# Pro-Mini-Candy.net
KiCad netlist of a schematic drawn in EAGLE
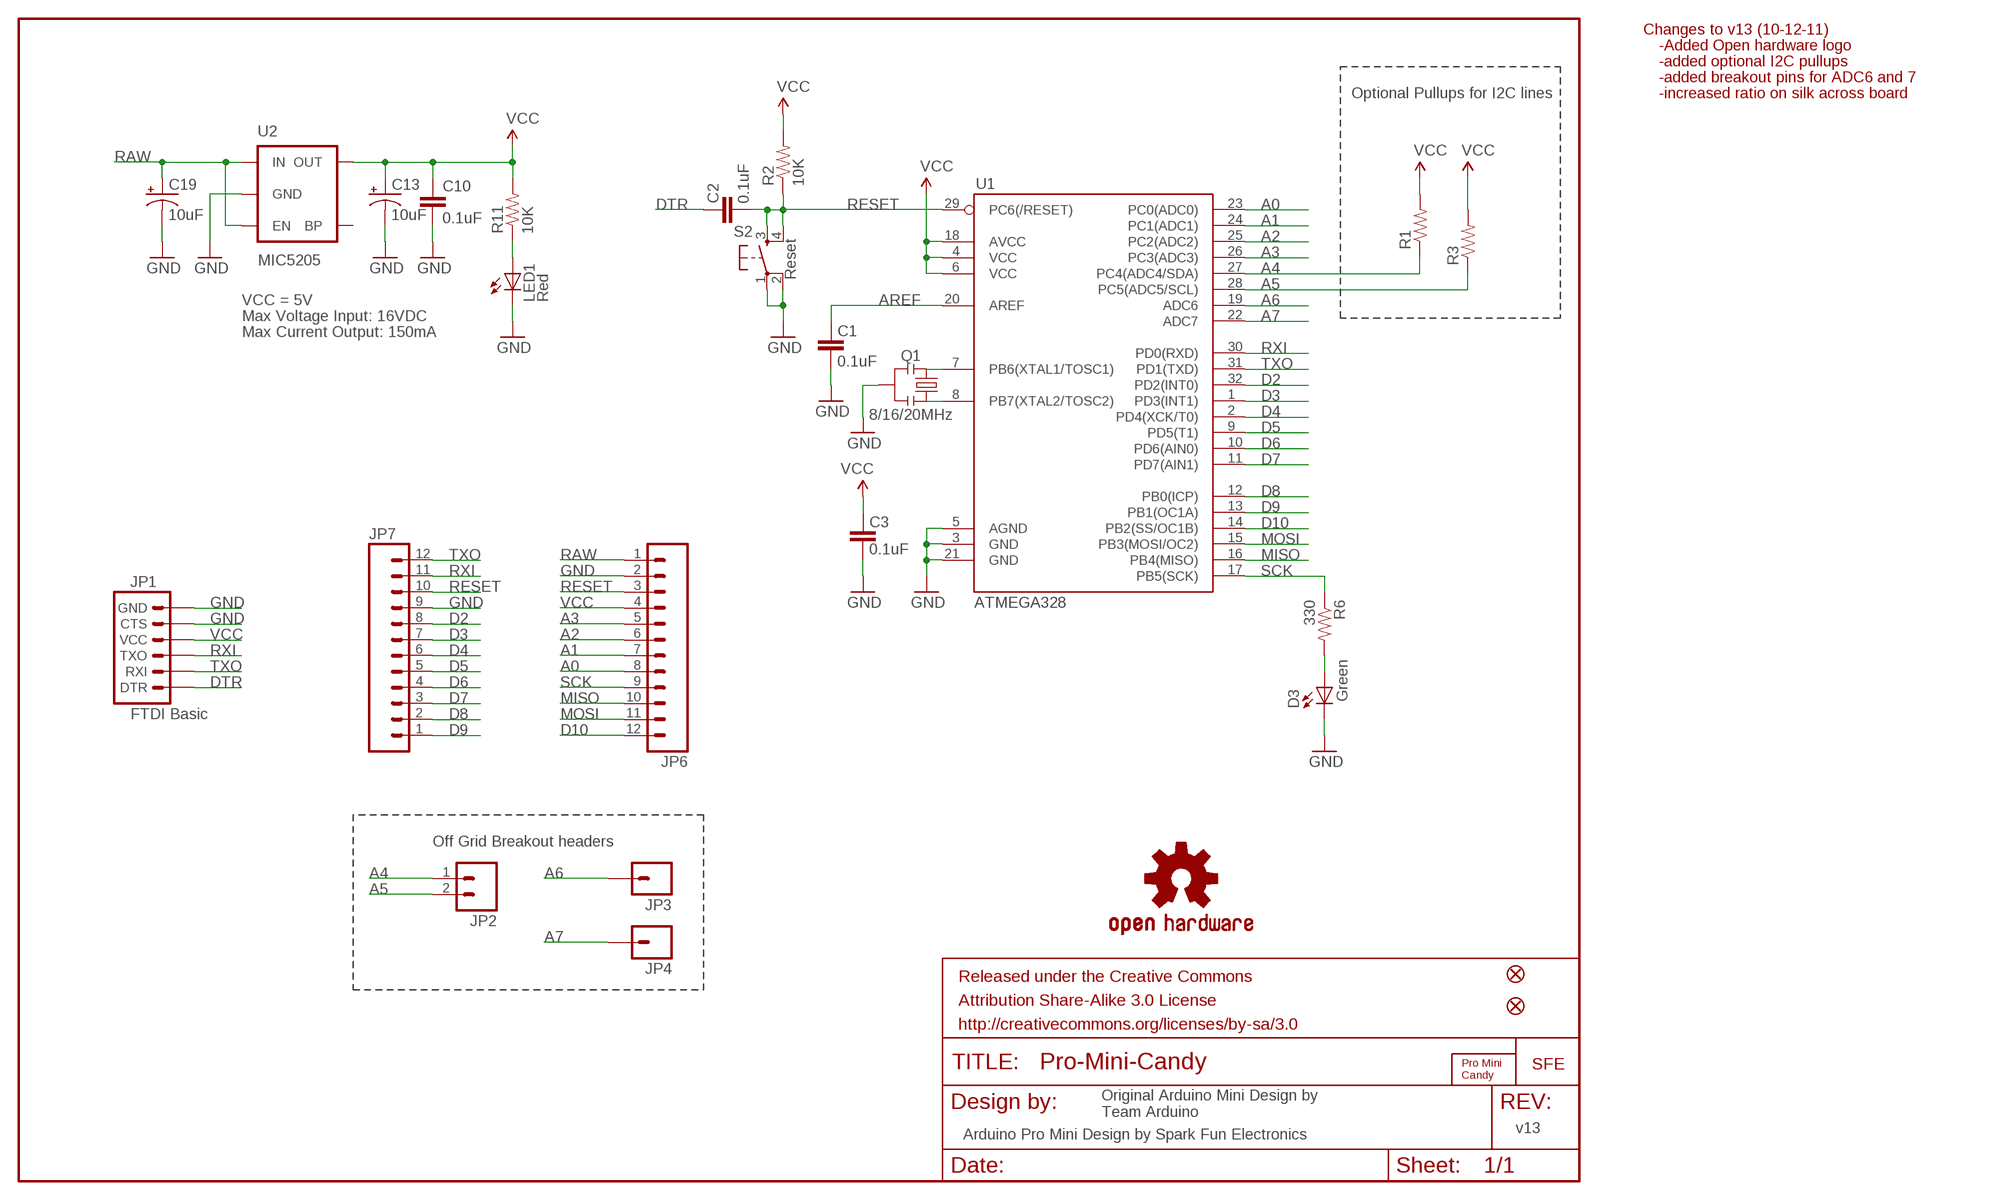
[diagram p0: schematic, sheet 1]

(export (version "E")
  (design (tool "Eeschema 10.0.6"))
  (components
    (comp (ref "C1")
      (value "0.1uF")
      (footprint "eagle-import:0402-CAP")
      (libsource (lib "eagle-import") (part "CAP0402-CAP"))
    )
    (comp (ref "C2")
      (value "0.1uF")
      (footprint "eagle-import:0402-CAP")
      (libsource (lib "eagle-import") (part "CAP0402-CAP"))
    )
    (comp (ref "C3")
      (value "0.1uF")
      (footprint "eagle-import:0402-CAP")
      (libsource (lib "eagle-import") (part "CAP0402-CAP"))
    )
    (comp (ref "C10")
      (value "0.1uF")
      (footprint "eagle-import:0402-CAP")
      (libsource (lib "eagle-import") (part "CAP0402-CAP"))
    )
    (comp (ref "C13")
      (value "10uF")
      (footprint "eagle-import:EIA3216")
      (libsource (lib "eagle-import") (part "CAP_POL1206"))
    )
    (comp (ref "C19")
      (value "10uF")
      (footprint "eagle-import:EIA3216")
      (libsource (lib "eagle-import") (part "CAP_POL1206"))
    )
    (comp (ref "D3")
      (value "Green")
      (footprint "eagle-import:LED-0603")
      (libsource (lib "eagle-import") (part "LED0603"))
    )
    (comp (ref "FRAME1")
      (value "FRAME-LETTER")
      (footprint "eagle-import:CREATIVE_COMMONS")
      (libsource (lib "eagle-import") (part "FRAME-LETTER"))
    )
    (comp (ref "JP1")
      (value "FTDI Basic")
      (footprint "eagle-import:1X06")
      (libsource (lib "eagle-import") (part "ARDUINO_SERIAL_PROGRAMPTH"))
    )
    (comp (ref "JP2")
      (value "M02PTH")
      (footprint "eagle-import:1X02")
      (libsource (lib "eagle-import") (part "M02PTH"))
    )
    (comp (ref "JP3")
      (value "M01PTH")
      (footprint "eagle-import:1X01")
      (libsource (lib "eagle-import") (part "M01PTH"))
    )
    (comp (ref "JP4")
      (value "M01PTH")
      (footprint "eagle-import:1X01")
      (libsource (lib "eagle-import") (part "M01PTH"))
    )
    (comp (ref "JP5")
      (value "FIDUCIALUFIDUCIAL")
      (footprint "eagle-import:MICRO-FIDUCIAL")
      (libsource (lib "eagle-import") (part "FIDUCIALUFIDUCIAL"))
    )
    (comp (ref "JP6")
      (value "M12PTH")
      (footprint "eagle-import:1X12")
      (libsource (lib "eagle-import") (part "M12PTH"))
    )
    (comp (ref "JP7")
      (value "M12PTH")
      (footprint "eagle-import:1X12")
      (libsource (lib "eagle-import") (part "M12PTH"))
    )
    (comp (ref "JP8")
      (value "FIDUCIALUFIDUCIAL")
      (footprint "eagle-import:MICRO-FIDUCIAL")
      (libsource (lib "eagle-import") (part "FIDUCIALUFIDUCIAL"))
    )
    (comp (ref "LED1")
      (value "Red")
      (footprint "eagle-import:LED-0603")
      (libsource (lib "eagle-import") (part "LED0603"))
    )
    (comp (ref "Q1")
      (value "8/16/20MHz")
      (footprint "eagle-import:RESONATOR-SMD")
      (libsource (lib "eagle-import") (part "RESONATORSMD"))
    )
    (comp (ref "R1")
      (value "RESISTOR0402-RES")
      (footprint "eagle-import:0402-RES")
      (libsource (lib "eagle-import") (part "RESISTOR0402-RES"))
    )
    (comp (ref "R2")
      (value "10K")
      (footprint "eagle-import:0402-RES")
      (libsource (lib "eagle-import") (part "RESISTOR0402-RES"))
    )
    (comp (ref "R3")
      (value "RESISTOR0402-RES")
      (footprint "eagle-import:0402-RES")
      (libsource (lib "eagle-import") (part "RESISTOR0402-RES"))
    )
    (comp (ref "R6")
      (value "330")
      (footprint "eagle-import:0402-RES")
      (libsource (lib "eagle-import") (part "RESISTOR0402-RES"))
    )
    (comp (ref "R11")
      (value "10K")
      (footprint "eagle-import:0402-RES")
      (libsource (lib "eagle-import") (part "RESISTOR0402-RES"))
    )
    (comp (ref "S2")
      (value "Reset")
      (footprint "eagle-import:TACTILE_SWITCH_SMD")
      (libsource (lib "eagle-import") (part "TAC_SWITCHSMD"))
    )
    (comp (ref "U$1")
      (value "LOGO-SFESK")
      (footprint "eagle-import:SFE-LOGO-FLAME")
      (libsource (lib "eagle-import") (part "LOGO-SFESK"))
    )
    (comp (ref "U$2")
      (value "PRO_MINI_CANDY")
      (footprint "eagle-import:PRO_MINI_CANDY")
      (libsource (lib "eagle-import") (part "PRO_MINI_CANDY"))
    )
    (comp (ref "U$3")
      (value "OSHW-LOGOS")
      (footprint "eagle-import:OSHW-LOGO-S")
      (libsource (lib "eagle-import") (part "OSHW-LOGOS"))
    )
    (comp (ref "U1")
      (value "ATMEGA328")
      (footprint "eagle-import:TQFP32-08")
      (libsource (lib "eagle-import") (part "ATMEGA168"))
    )
    (comp (ref "U2")
      (value "MIC5205")
      (footprint "eagle-import:SOT23-5")
      (libsource (lib "eagle-import") (part "V_REG_LDOSMD"))
    )
  )
  (nets
    (net (code "1") (name "/A0") (class "Default")
      (node (ref "JP6") (pin "8") (pinfunction "8_8") (pintype "passive"))
      (node (ref "U1") (pin "23") (pinfunction "PC0(ADC0)_23") (pintype "bidirectional"))
    )
    (net (code "2") (name "/A1") (class "Default")
      (node (ref "JP6") (pin "7") (pinfunction "7_7") (pintype "passive"))
      (node (ref "U1") (pin "24") (pinfunction "PC1(ADC1)_24") (pintype "bidirectional"))
    )
    (net (code "3") (name "/A2") (class "Default")
      (node (ref "JP6") (pin "6") (pinfunction "6_6") (pintype "passive"))
      (node (ref "U1") (pin "25") (pinfunction "PC2(ADC2)_25") (pintype "bidirectional"))
    )
    (net (code "4") (name "/A3") (class "Default")
      (node (ref "JP6") (pin "5") (pinfunction "5_5") (pintype "passive"))
      (node (ref "U1") (pin "26") (pinfunction "PC3(ADC3)_26") (pintype "bidirectional"))
    )
    (net (code "5") (name "/A4") (class "Default")
      (node (ref "JP2") (pin "1") (pinfunction "1_1") (pintype "passive"))
      (node (ref "R1") (pin "1") (pinfunction "1_1") (pintype "passive"))
      (node (ref "U1") (pin "27") (pinfunction "PC4(ADC4/SDA)_27") (pintype "bidirectional"))
    )
    (net (code "6") (name "/A5") (class "Default")
      (node (ref "JP2") (pin "2") (pinfunction "2_2") (pintype "passive"))
      (node (ref "R3") (pin "1") (pinfunction "1_1") (pintype "passive"))
      (node (ref "U1") (pin "28") (pinfunction "PC5(ADC5/SCL)_28") (pintype "bidirectional"))
    )
    (net (code "7") (name "/A6") (class "Default")
      (node (ref "JP3") (pin "1") (pinfunction "1_1") (pintype "passive"))
      (node (ref "U1") (pin "19") (pinfunction "ADC6_19") (pintype "bidirectional"))
    )
    (net (code "8") (name "/A7") (class "Default")
      (node (ref "JP4") (pin "1") (pinfunction "1_1") (pintype "passive"))
      (node (ref "U1") (pin "22") (pinfunction "ADC7_22") (pintype "bidirectional"))
    )
    (net (code "9") (name "/AREF") (class "Default")
      (node (ref "C1") (pin "2") (pinfunction "2_2") (pintype "passive"))
      (node (ref "U1") (pin "20") (pinfunction "AREF_20") (pintype "bidirectional"))
    )
    (net (code "10") (name "/D2") (class "Default")
      (node (ref "JP7") (pin "8") (pinfunction "8_8") (pintype "passive"))
      (node (ref "U1") (pin "32") (pinfunction "PD2(INT0)_32") (pintype "bidirectional"))
    )
    (net (code "11") (name "/D3") (class "Default")
      (node (ref "JP7") (pin "7") (pinfunction "7_7") (pintype "passive"))
      (node (ref "U1") (pin "1") (pinfunction "PD3(INT1)_1") (pintype "bidirectional"))
    )
    (net (code "12") (name "/D4") (class "Default")
      (node (ref "JP7") (pin "6") (pinfunction "6_6") (pintype "passive"))
      (node (ref "U1") (pin "2") (pinfunction "PD4(XCK/T0)_2") (pintype "bidirectional"))
    )
    (net (code "13") (name "/D5") (class "Default")
      (node (ref "JP7") (pin "5") (pinfunction "5_5") (pintype "passive"))
      (node (ref "U1") (pin "9") (pinfunction "PD5(T1)_9") (pintype "bidirectional"))
    )
    (net (code "14") (name "/D6") (class "Default")
      (node (ref "JP7") (pin "4") (pinfunction "4_4") (pintype "passive"))
      (node (ref "U1") (pin "10") (pinfunction "PD6(AIN0)_10") (pintype "bidirectional"))
    )
    (net (code "15") (name "/D7") (class "Default")
      (node (ref "JP7") (pin "3") (pinfunction "3_3") (pintype "passive"))
      (node (ref "U1") (pin "11") (pinfunction "PD7(AIN1)_11") (pintype "bidirectional"))
    )
    (net (code "16") (name "/D8") (class "Default")
      (node (ref "JP7") (pin "2") (pinfunction "2_2") (pintype "passive"))
      (node (ref "U1") (pin "12") (pinfunction "PB0(ICP)_12") (pintype "bidirectional"))
    )
    (net (code "17") (name "/D9") (class "Default")
      (node (ref "JP7") (pin "1") (pinfunction "1_1") (pintype "passive"))
      (node (ref "U1") (pin "13") (pinfunction "PB1(OC1A)_13") (pintype "bidirectional"))
    )
    (net (code "18") (name "/D10") (class "Default")
      (node (ref "JP6") (pin "12") (pinfunction "12_12") (pintype "passive"))
      (node (ref "U1") (pin "14") (pinfunction "PB2(SS/OC1B)_14") (pintype "bidirectional"))
    )
    (net (code "19") (name "/DTR") (class "Default")
      (node (ref "C2") (pin "2") (pinfunction "2_2") (pintype "passive"))
      (node (ref "JP1") (pin "1") (pinfunction "DTR_1") (pintype "passive"))
    )
    (net (code "20") (name "/MISO") (class "Default")
      (node (ref "JP6") (pin "10") (pinfunction "10_10") (pintype "passive"))
      (node (ref "U1") (pin "16") (pinfunction "PB4(MISO)_16") (pintype "bidirectional"))
    )
    (net (code "21") (name "/MOSI") (class "Default")
      (node (ref "JP6") (pin "11") (pinfunction "11_11") (pintype "passive"))
      (node (ref "U1") (pin "15") (pinfunction "PB3(MOSI/OC2)_15") (pintype "bidirectional"))
    )
    (net (code "22") (name "/RAW") (class "Default")
      (node (ref "C19") (pin "A") (pinfunction "+_A") (pintype "passive"))
      (node (ref "JP6") (pin "1") (pinfunction "1_1") (pintype "passive"))
      (node (ref "U2") (pin "1") (pinfunction "IN_1") (pintype "input"))
      (node (ref "U2") (pin "3") (pinfunction "EN_3") (pintype "input"))
    )
    (net (code "23") (name "/RESET") (class "Default")
      (node (ref "C2") (pin "1") (pinfunction "1_1") (pintype "passive"))
      (node (ref "JP6") (pin "3") (pinfunction "3_3") (pintype "passive"))
      (node (ref "JP7") (pin "10") (pinfunction "10_10") (pintype "passive"))
      (node (ref "R2") (pin "1") (pinfunction "1_1") (pintype "passive"))
      (node (ref "S2") (pin "3") (pinfunction "3_3") (pintype "passive"))
      (node (ref "S2") (pin "4") (pinfunction "4_4") (pintype "passive"))
      (node (ref "U1") (pin "29") (pinfunction "PC6(/RESET)_29") (pintype "bidirectional"))
    )
    (net (code "24") (name "/RXI") (class "Default")
      (node (ref "JP1") (pin "3") (pinfunction "TXO_3") (pintype "passive"))
      (node (ref "JP7") (pin "11") (pinfunction "11_11") (pintype "passive"))
      (node (ref "U1") (pin "30") (pinfunction "PD0(RXD)_30") (pintype "bidirectional"))
    )
    (net (code "25") (name "/SCK") (class "Default")
      (node (ref "JP6") (pin "9") (pinfunction "9_9") (pintype "passive"))
      (node (ref "R6") (pin "1") (pinfunction "1_1") (pintype "passive"))
      (node (ref "U1") (pin "17") (pinfunction "PB5(SCK)_17") (pintype "bidirectional"))
    )
    (net (code "26") (name "/TXO") (class "Default")
      (node (ref "JP1") (pin "2") (pinfunction "RXI_2") (pintype "passive"))
      (node (ref "JP7") (pin "12") (pinfunction "12_12") (pintype "passive"))
      (node (ref "U1") (pin "31") (pinfunction "PD1(TXD)_31") (pintype "bidirectional"))
    )
    (net (code "27") (name "GND") (class "Default")
      (node (ref "C1") (pin "1") (pinfunction "1_1") (pintype "passive"))
      (node (ref "C10") (pin "2") (pinfunction "2_2") (pintype "passive"))
      (node (ref "C13") (pin "C") (pinfunction "-_C") (pintype "passive"))
      (node (ref "C19") (pin "C") (pinfunction "-_C") (pintype "passive"))
      (node (ref "C3") (pin "1") (pinfunction "1_1") (pintype "passive"))
      (node (ref "D3") (pin "C") (pinfunction "C_C") (pintype "passive"))
      (node (ref "JP1") (pin "5") (pinfunction "CTS_5") (pintype "passive"))
      (node (ref "JP1") (pin "6") (pinfunction "GND_6") (pintype "passive"))
      (node (ref "JP6") (pin "2") (pinfunction "2_2") (pintype "passive"))
      (node (ref "JP7") (pin "9") (pinfunction "9_9") (pintype "passive"))
      (node (ref "LED1") (pin "C") (pinfunction "C_C") (pintype "passive"))
      (node (ref "Q1") (pin "2") (pinfunction "2_2") (pintype "passive"))
      (node (ref "S2") (pin "1") (pinfunction "1_1") (pintype "passive"))
      (node (ref "S2") (pin "2") (pinfunction "2_2") (pintype "passive"))
      (node (ref "U1") (pin "21") (pinfunction "GND_21") (pintype "bidirectional"))
      (node (ref "U1") (pin "3") (pinfunction "GND_3") (pintype "bidirectional"))
      (node (ref "U1") (pin "5") (pinfunction "AGND_5") (pintype "bidirectional"))
      (node (ref "U2") (pin "2") (pinfunction "GND_2") (pintype "input"))
    )
    (net (code "28") (name "Net-(D3-PadA)") (class "Default")
      (node (ref "D3") (pin "A") (pinfunction "A_A") (pintype "passive"))
      (node (ref "R6") (pin "2") (pinfunction "2_2") (pintype "passive"))
    )
    (net (code "29") (name "Net-(LED1-PadA)") (class "Default")
      (node (ref "LED1") (pin "A") (pinfunction "A_A") (pintype "passive"))
      (node (ref "R11") (pin "1") (pinfunction "1_1") (pintype "passive"))
    )
    (net (code "30") (name "Net-(U1-PB6(XTAL1{slash}TOSC1))") (class "Default")
      (node (ref "Q1") (pin "3") (pinfunction "3_3") (pintype "passive"))
      (node (ref "U1") (pin "7") (pinfunction "PB6(XTAL1/TOSC1)_7") (pintype "bidirectional"))
    )
    (net (code "31") (name "Net-(U1-PB7(XTAL2{slash}TOSC2))") (class "Default")
      (node (ref "Q1") (pin "1") (pinfunction "1_1") (pintype "passive"))
      (node (ref "U1") (pin "8") (pinfunction "PB7(XTAL2/TOSC2)_8") (pintype "bidirectional"))
    )
    (net (code "32") (name "VCC") (class "Default")
      (node (ref "C10") (pin "1") (pinfunction "1_1") (pintype "passive"))
      (node (ref "C13") (pin "A") (pinfunction "+_A") (pintype "passive"))
      (node (ref "C3") (pin "2") (pinfunction "2_2") (pintype "passive"))
      (node (ref "JP1") (pin "4") (pinfunction "VCC_4") (pintype "passive"))
      (node (ref "JP6") (pin "4") (pinfunction "4_4") (pintype "passive"))
      (node (ref "R1") (pin "2") (pinfunction "2_2") (pintype "passive"))
      (node (ref "R11") (pin "2") (pinfunction "2_2") (pintype "passive"))
      (node (ref "R2") (pin "2") (pinfunction "2_2") (pintype "passive"))
      (node (ref "R3") (pin "2") (pinfunction "2_2") (pintype "passive"))
      (node (ref "U1") (pin "18") (pinfunction "AVCC_18") (pintype "bidirectional"))
      (node (ref "U1") (pin "4") (pinfunction "VCC_4") (pintype "bidirectional"))
      (node (ref "U1") (pin "6") (pinfunction "VCC_6") (pintype "bidirectional"))
      (node (ref "U2") (pin "5") (pinfunction "OUT_5") (pintype "passive"))
    )
    (net (code "33") (name "unconnected-(U2-BP-Pad4)") (class "Default")
      (node (ref "U2") (pin "4") (pinfunction "BP_4") (pintype "input"))
    )
  )
)
